# RF.net
KiCad netlist of a schematic drawn in Altium Designer
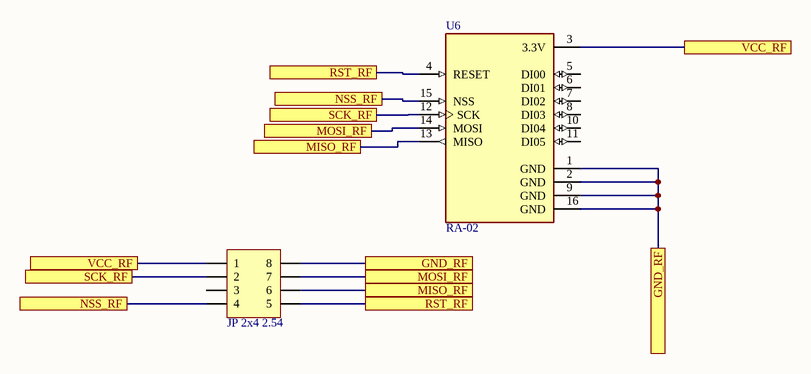
[diagram p0: RF.SchDoc]

(export (version "E")
  (design (tool "Eeschema 10.0.6"))
  (components
    (comp (ref "JP1")
      (value "JP 2x4 2.54")
      (footprint "JP 2x4 CT")
      (description "Cắm")
      (libsource (lib "Altium_Lib_by_KhueNguyenCreator") (part "JP 2x4 2.54 Cai Thang"))
    )
    (comp (ref "U6")
      (value "RA-02")
      (footprint "RA-02")
      (fields (field (name "MF") "Ai-Thinker"))
      (libsource (lib "RA-02") (part "RA-02"))
    )
  )
  (nets
    (net (code "1") (name "/GND_RF") (class "Default")
      (node (ref "JP1") (pin "8") (pinfunction "8_8") (pintype "passive"))
      (node (ref "U6") (pin "1") (pinfunction "GND_1") (pintype "power_in"))
      (node (ref "U6") (pin "16") (pinfunction "GND_16") (pintype "power_in"))
      (node (ref "U6") (pin "2") (pinfunction "GND_2") (pintype "power_in"))
      (node (ref "U6") (pin "9") (pinfunction "GND_9") (pintype "power_in"))
    )
    (net (code "2") (name "/MISO_RF") (class "Default")
      (node (ref "JP1") (pin "6") (pinfunction "6_6") (pintype "passive"))
      (node (ref "U6") (pin "13") (pinfunction "MISO_13") (pintype "output"))
    )
    (net (code "3") (name "/MOSI_RF") (class "Default")
      (node (ref "JP1") (pin "7") (pinfunction "7_7") (pintype "passive"))
      (node (ref "U6") (pin "14") (pinfunction "MOSI_14") (pintype "input"))
    )
    (net (code "4") (name "/NSS_RF") (class "Default")
      (node (ref "JP1") (pin "4") (pinfunction "4_4") (pintype "passive"))
      (node (ref "U6") (pin "15") (pinfunction "NSS_15") (pintype "input"))
    )
    (net (code "5") (name "/RST_RF") (class "Default")
      (node (ref "JP1") (pin "5") (pinfunction "5_5") (pintype "passive"))
      (node (ref "U6") (pin "4") (pinfunction "RESET_4") (pintype "input"))
    )
    (net (code "6") (name "/SCK_RF") (class "Default")
      (node (ref "JP1") (pin "2") (pinfunction "2_2") (pintype "passive"))
      (node (ref "U6") (pin "12") (pinfunction "SCK_12") (pintype "input"))
    )
    (net (code "7") (name "/VCC_RF") (class "Default")
      (node (ref "JP1") (pin "1") (pinfunction "1_1") (pintype "passive"))
      (node (ref "U6") (pin "3") (pinfunction "3.3V_3") (pintype "power_in"))
    )
    (net (code "8") (name "unconnected-(JP1-Pad3)") (class "Default")
      (node (ref "JP1") (pin "3") (pinfunction "3_3") (pintype "passive"))
    )
    (net (code "9") (name "unconnected-(U6-DI00-Pad5)") (class "Default")
      (node (ref "U6") (pin "5") (pinfunction "DI00_5") (pintype "bidirectional"))
    )
    (net (code "10") (name "unconnected-(U6-DI01-Pad6)") (class "Default")
      (node (ref "U6") (pin "6") (pinfunction "DI01_6") (pintype "bidirectional"))
    )
    (net (code "11") (name "unconnected-(U6-DI02-Pad7)") (class "Default")
      (node (ref "U6") (pin "7") (pinfunction "DI02_7") (pintype "bidirectional"))
    )
    (net (code "12") (name "unconnected-(U6-DI03-Pad8)") (class "Default")
      (node (ref "U6") (pin "8") (pinfunction "DI03_8") (pintype "bidirectional"))
    )
    (net (code "13") (name "unconnected-(U6-DI04-Pad10)") (class "Default")
      (node (ref "U6") (pin "10") (pinfunction "DI04_10") (pintype "bidirectional"))
    )
    (net (code "14") (name "unconnected-(U6-DI05-Pad11)") (class "Default")
      (node (ref "U6") (pin "11") (pinfunction "DI05_11") (pintype "bidirectional"))
    )
  )
)
